# dboard.net
KiCad netlist of a schematic drawn in EAGLE
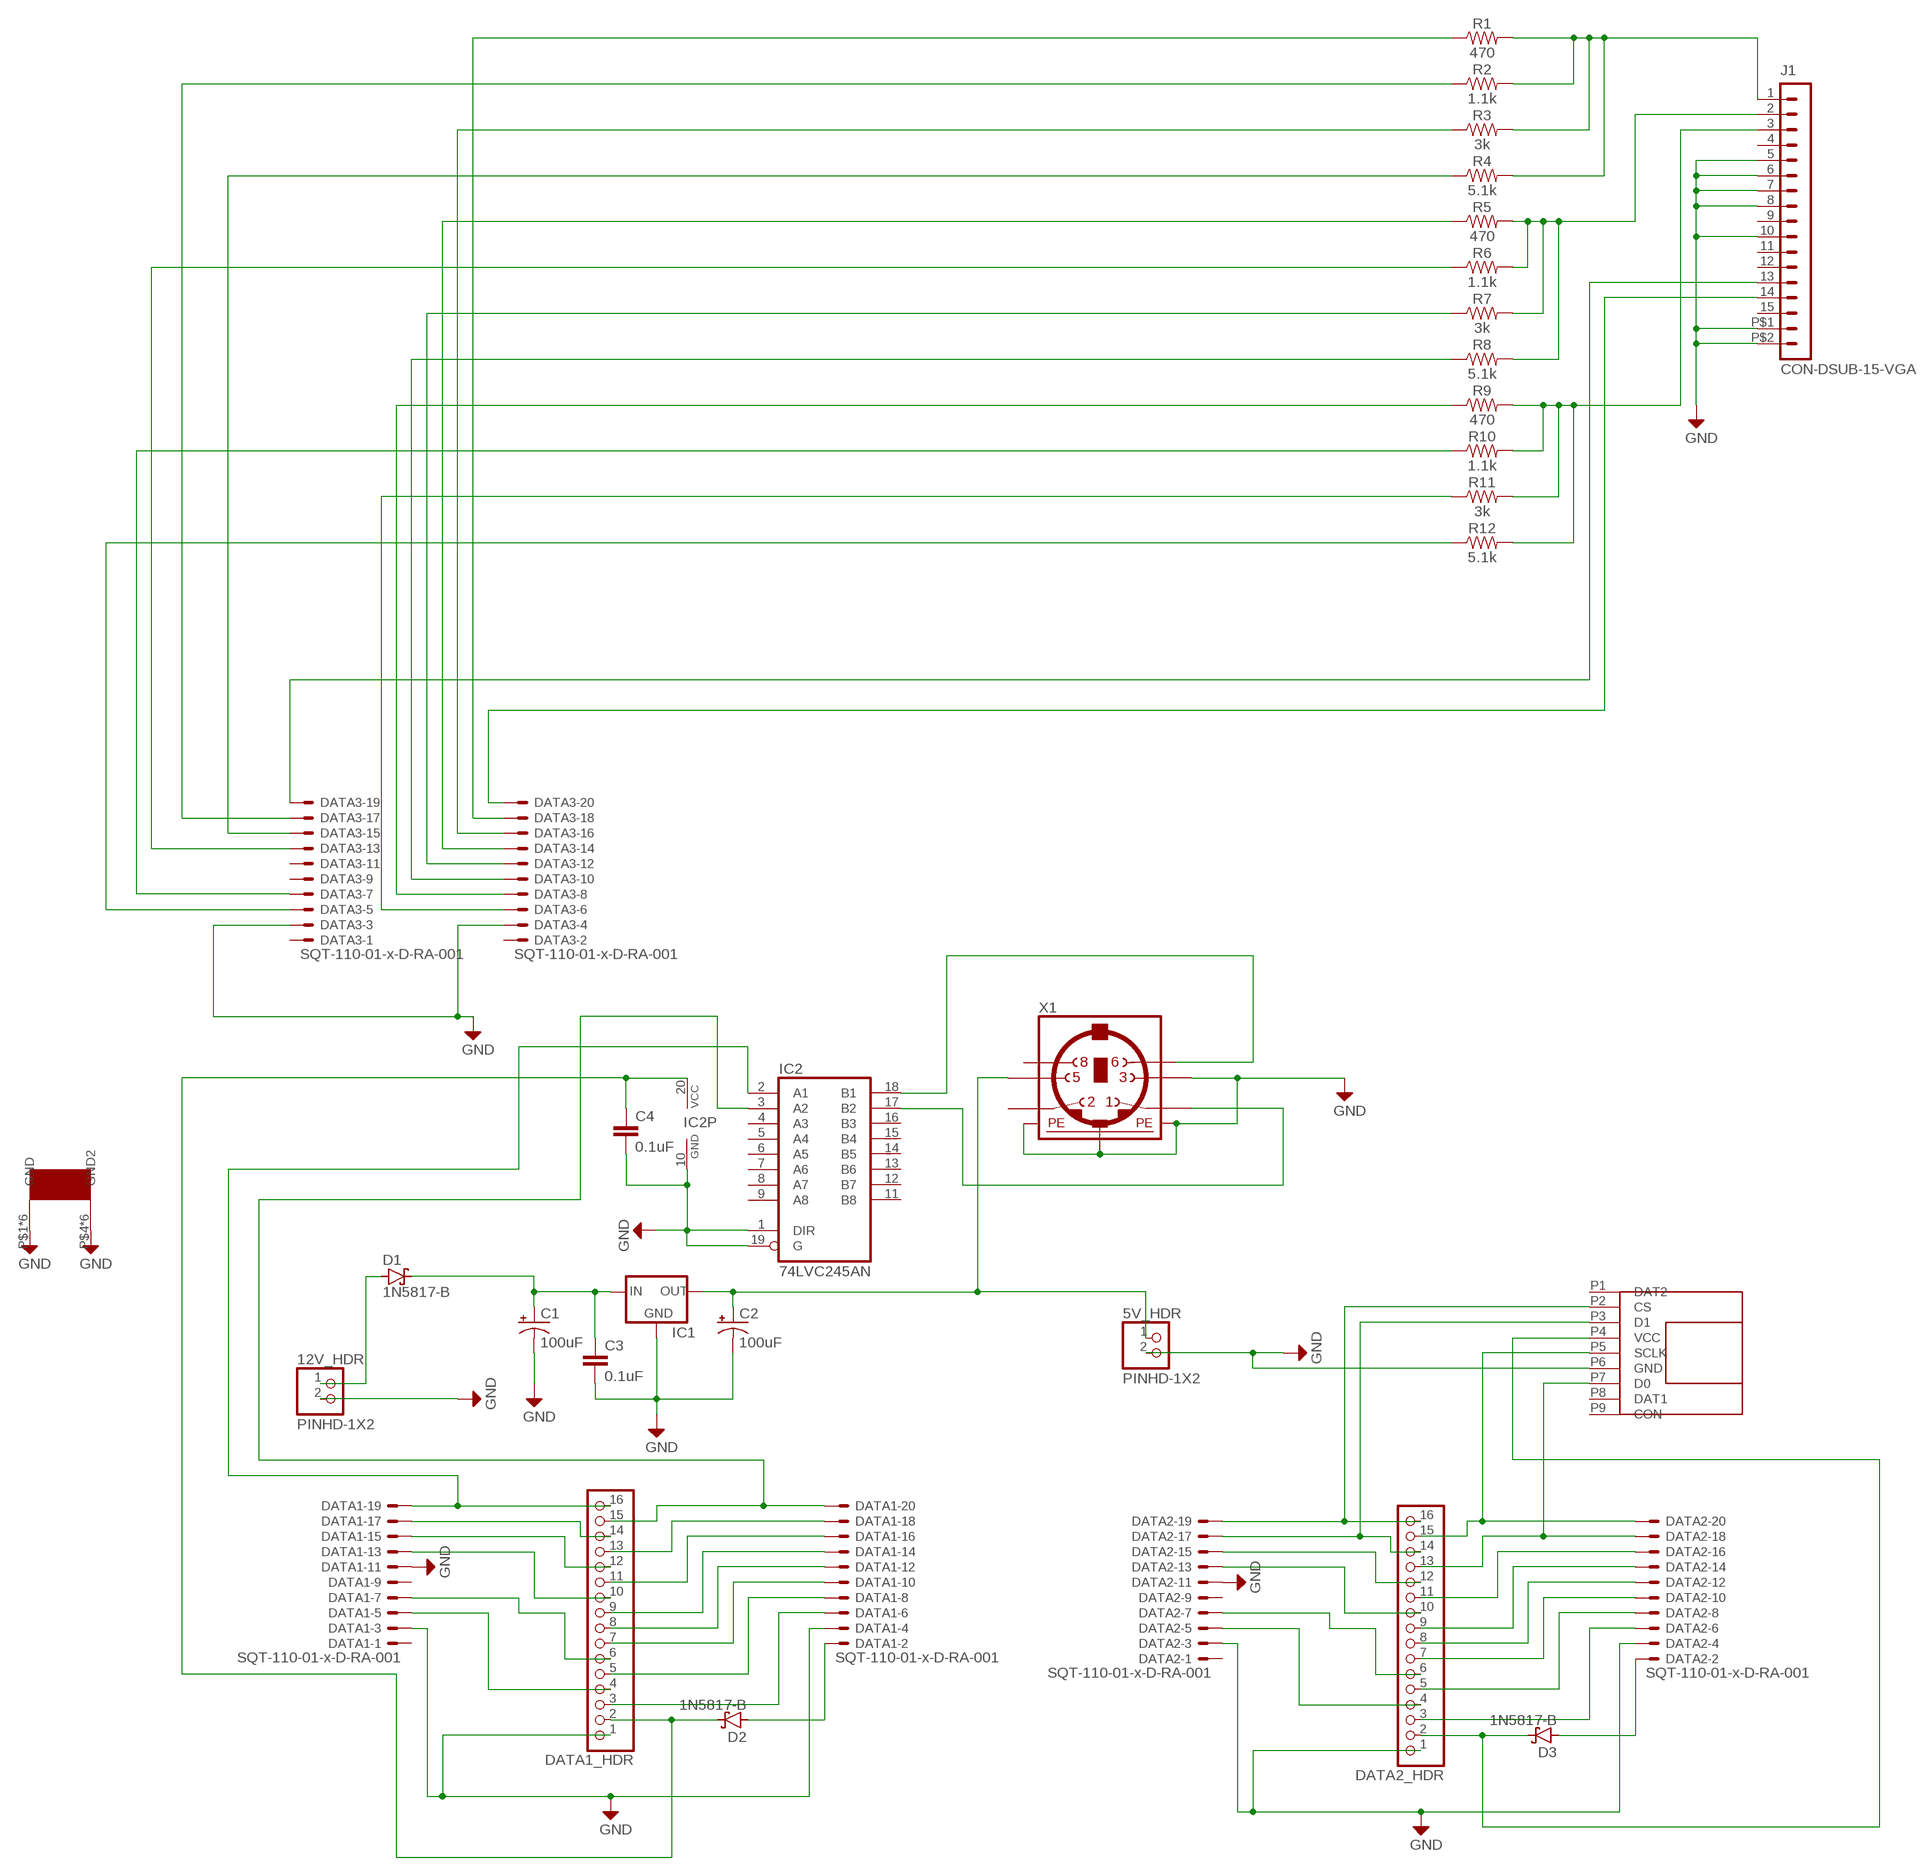
[diagram p0: schematic, sheet 1]

(export (version "E")
  (design (tool "Eeschema 10.0.6"))
  (components
    (comp (ref "5V_HDR")
      (value "PINHD-1X2")
      (footprint "eagle-import:1X02")
      (libsource (lib "eagle-import") (part "PINHD-1X2"))
    )
    (comp (ref "12V_HDR")
      (value "PINHD-1X2")
      (footprint "eagle-import:1X02")
      (libsource (lib "eagle-import") (part "PINHD-1X2"))
    )
    (comp (ref "C1")
      (value "100uF")
      (footprint "eagle-import:CPOL-RADIAL-2.5MM-6.5MM")
      (libsource (lib "eagle-import") (part "100UF-POLAR-RADIAL-2.5MM-25V-20%"))
    )
    (comp (ref "C2")
      (value "100uF")
      (footprint "eagle-import:CPOL-RADIAL-2.5MM-6.5MM")
      (libsource (lib "eagle-import") (part "100UF-POLAR-RADIAL-2.5MM-25V-20%"))
    )
    (comp (ref "C3")
      (value "0.1uF")
      (footprint "eagle-import:CAP-PTH-SMALL-KIT")
      (libsource (lib "eagle-import") (part "0.1UF-KIT-EZ-50V-20%"))
    )
    (comp (ref "C4")
      (value "0.1uF")
      (footprint "eagle-import:CAP-PTH-SMALL-KIT")
      (libsource (lib "eagle-import") (part "0.1UF-KIT-EZ-50V-20%"))
    )
    (comp (ref "D1")
      (value "1N5817-B")
      (footprint "eagle-import:DO41-7.6")
      (libsource (lib "eagle-import") (part "1N5817-B"))
    )
    (comp (ref "D2")
      (value "1N5817-B")
      (footprint "eagle-import:DO41-7.6")
      (libsource (lib "eagle-import") (part "1N5817-B"))
    )
    (comp (ref "D3")
      (value "1N5817-B")
      (footprint "eagle-import:DO41-7.6")
      (libsource (lib "eagle-import") (part "1N5817-B"))
    )
    (comp (ref "DATA1")
      (value "SQT-110-01-x-D-RA-001")
      (footprint "eagle-import:332-20")
      (libsource (lib "eagle-import") (part "332-20"))
    )
    (comp (ref "DATA1_HDR")
      (value "PINHD-1X16")
      (footprint "eagle-import:1X16")
      (libsource (lib "eagle-import") (part "PINHD-1X16"))
    )
    (comp (ref "DATA2")
      (value "SQT-110-01-x-D-RA-001")
      (footprint "eagle-import:332-20")
      (libsource (lib "eagle-import") (part "332-20"))
    )
    (comp (ref "DATA2_HDR")
      (value "PINHD-1X16")
      (footprint "eagle-import:1X16")
      (libsource (lib "eagle-import") (part "PINHD-1X16"))
    )
    (comp (ref "DATA3")
      (value "SQT-110-01-x-D-RA-001")
      (footprint "eagle-import:332-20")
      (libsource (lib "eagle-import") (part "332-20"))
    )
    (comp (ref "IC1")
      (value "78XXL")
      (footprint "eagle-import:78XXL")
      (libsource (lib "eagle-import") (part "78XXL"))
    )
    (comp (ref "IC2")
      (value "74LVC245AN")
      (footprint "eagle-import:DIL20")
      (libsource (lib "eagle-import") (part "74245NLS"))
    )
    (comp (ref "J1")
      (value "CON-DSUB-15-VGA")
      (footprint "eagle-import:181-015-212-171")
      (libsource (lib "eagle-import") (part "CON-DSUB-15-VGA"))
    )
    (comp (ref "R1")
      (value "470")
      (footprint "eagle-import:AXIAL-0.3")
      (libsource (lib "eagle-import") (part "RESISTORAXIAL-0.3"))
    )
    (comp (ref "R2")
      (value "1.1k")
      (footprint "eagle-import:AXIAL-0.3")
      (libsource (lib "eagle-import") (part "RESISTORAXIAL-0.3"))
    )
    (comp (ref "R3")
      (value "3k")
      (footprint "eagle-import:AXIAL-0.3")
      (libsource (lib "eagle-import") (part "RESISTORAXIAL-0.3"))
    )
    (comp (ref "R4")
      (value "5.1k")
      (footprint "eagle-import:AXIAL-0.3")
      (libsource (lib "eagle-import") (part "RESISTORAXIAL-0.3"))
    )
    (comp (ref "R5")
      (value "470")
      (footprint "eagle-import:AXIAL-0.3")
      (libsource (lib "eagle-import") (part "RESISTORAXIAL-0.3"))
    )
    (comp (ref "R6")
      (value "1.1k")
      (footprint "eagle-import:AXIAL-0.3")
      (libsource (lib "eagle-import") (part "RESISTORAXIAL-0.3"))
    )
    (comp (ref "R7")
      (value "3k")
      (footprint "eagle-import:AXIAL-0.3")
      (libsource (lib "eagle-import") (part "RESISTORAXIAL-0.3"))
    )
    (comp (ref "R8")
      (value "5.1k")
      (footprint "eagle-import:AXIAL-0.3")
      (libsource (lib "eagle-import") (part "RESISTORAXIAL-0.3"))
    )
    (comp (ref "R9")
      (value "470")
      (footprint "eagle-import:AXIAL-0.3")
      (libsource (lib "eagle-import") (part "RESISTORAXIAL-0.3"))
    )
    (comp (ref "R10")
      (value "1.1k")
      (footprint "eagle-import:AXIAL-0.3")
      (libsource (lib "eagle-import") (part "RESISTORAXIAL-0.3"))
    )
    (comp (ref "R11")
      (value "3k")
      (footprint "eagle-import:AXIAL-0.3")
      (libsource (lib "eagle-import") (part "RESISTORAXIAL-0.3"))
    )
    (comp (ref "R12")
      (value "5.1k")
      (footprint "eagle-import:AXIAL-0.3")
      (libsource (lib "eagle-import") (part "RESISTORAXIAL-0.3"))
    )
    (comp (ref "U$1")
      (value "7085THERMALPAD")
      (footprint "eagle-import:7805THERMALPAD")
      (libsource (lib "eagle-import") (part "7085THERMALPAD"))
    )
    (comp (ref "U$2")
      (value "TF_CARD_BREAKOUT")
      (footprint "eagle-import:OPEN-SMARTTFCARDBREAKOUT")
      (libsource (lib "eagle-import") (part "OPEN-SMARTTFCARDBREAKOUT"))
    )
    (comp (ref "X1")
      (value "MINI_DIN_6")
      (footprint "eagle-import:M_DIN6")
      (libsource (lib "eagle-import") (part "MINI_DIN_6"))
    )
  )
  (nets
    (net (code "1") (name "GND") (class "Default")
      (node (ref "12V_HDR") (pin "2") (pinfunction "2_2") (pintype "passive"))
      (node (ref "5V_HDR") (pin "2") (pinfunction "2_2") (pintype "passive"))
      (node (ref "C1") (pin "2") (pinfunction "-_2") (pintype "passive"))
      (node (ref "C2") (pin "2") (pinfunction "-_2") (pintype "passive"))
      (node (ref "C3") (pin "2") (pinfunction "2_2") (pintype "passive"))
      (node (ref "C4") (pin "2") (pinfunction "2_2") (pintype "passive"))
      (node (ref "DATA1") (pin "11") (pinfunction "S_11") (pintype "passive"))
      (node (ref "DATA1") (pin "3") (pinfunction "S_3") (pintype "passive"))
      (node (ref "DATA1") (pin "4") (pinfunction "S_4") (pintype "passive"))
      (node (ref "DATA1_HDR") (pin "1") (pinfunction "1_1") (pintype "passive"))
      (node (ref "DATA2") (pin "11") (pinfunction "S_11") (pintype "passive"))
      (node (ref "DATA2") (pin "3") (pinfunction "S_3") (pintype "passive"))
      (node (ref "DATA2") (pin "4") (pinfunction "S_4") (pintype "passive"))
      (node (ref "DATA2_HDR") (pin "1") (pinfunction "1_1") (pintype "passive"))
      (node (ref "DATA3") (pin "3") (pinfunction "S_3") (pintype "passive"))
      (node (ref "DATA3") (pin "4") (pinfunction "S_4") (pintype "passive"))
      (node (ref "IC1") (pin "GND") (pinfunction "GND_GND") (pintype "input"))
      (node (ref "IC2") (pin "1") (pinfunction "DIR_1") (pintype "input"))
      (node (ref "IC2") (pin "10") (pinfunction "GND_10") (pintype "power_in"))
      (node (ref "IC2") (pin "19") (pinfunction "G_19") (pintype "input"))
      (node (ref "J1") (pin "10") (pinfunction "10_10") (pintype "passive"))
      (node (ref "J1") (pin "5") (pinfunction "5_5") (pintype "passive"))
      (node (ref "J1") (pin "6") (pinfunction "6_6") (pintype "passive"))
      (node (ref "J1") (pin "7") (pinfunction "7_7") (pintype "passive"))
      (node (ref "J1") (pin "8") (pinfunction "8_8") (pintype "passive"))
      (node (ref "J1") (pin "P$1") (pinfunction "16_P$1") (pintype "passive"))
      (node (ref "J1") (pin "P$2") (pinfunction "17_P$2") (pintype "passive"))
      (node (ref "U$1") (pin "P$1") (pinfunction "GND_P$1") (pintype "power_in"))
      (node (ref "U$1") (pin "P$10") (pinfunction "GND_P$10") (pintype "power_in"))
      (node (ref "U$1") (pin "P$11") (pinfunction "GND2_P$11") (pintype "power_in"))
      (node (ref "U$1") (pin "P$14") (pinfunction "GND2_P$14") (pintype "power_in"))
      (node (ref "U$1") (pin "P$19") (pinfunction "GND2_P$19") (pintype "power_in"))
      (node (ref "U$1") (pin "P$21") (pinfunction "GND2_P$21") (pintype "power_in"))
      (node (ref "U$1") (pin "P$24") (pinfunction "GND2_P$24") (pintype "power_in"))
      (node (ref "U$1") (pin "P$4") (pinfunction "GND2_P$4") (pintype "power_in"))
      (node (ref "U$1") (pin "P$6") (pinfunction "GND_P$6") (pintype "power_in"))
      (node (ref "U$1") (pin "P$7") (pinfunction "GND_P$7") (pintype "power_in"))
      (node (ref "U$1") (pin "P$8") (pinfunction "GND_P$8") (pintype "power_in"))
      (node (ref "U$1") (pin "P$9") (pinfunction "GND_P$9") (pintype "power_in"))
      (node (ref "U$2") (pin "P6") (pinfunction "GND_P6") (pintype "power_in"))
      (node (ref "X1") (pin "3") (pinfunction "3_3") (pintype "passive"))
      (node (ref "X1") (pin "SH1") (pinfunction "PE1_SH1") (pintype "power_in"))
      (node (ref "X1") (pin "SH2") (pinfunction "PE2_SH2") (pintype "power_in"))
      (node (ref "X1") (pin "SH3") (pinfunction "PE3_SH3") (pintype "power_in"))
    )
    (net (code "2") (name "Net-(12V_HDR-Pad1)") (class "Default")
      (node (ref "12V_HDR") (pin "1") (pinfunction "1_1") (pintype "passive"))
      (node (ref "D1") (pin "A") (pinfunction "A_A") (pintype "passive"))
    )
    (net (code "3") (name "Net-(C1-+)") (class "Default")
      (node (ref "C1") (pin "1") (pinfunction "+_1") (pintype "passive"))
      (node (ref "C3") (pin "1") (pinfunction "1_1") (pintype "passive"))
      (node (ref "D1") (pin "C") (pinfunction "C_C") (pintype "passive"))
      (node (ref "IC1") (pin "IN") (pinfunction "IN_IN") (pintype "input"))
    )
    (net (code "4") (name "Net-(C2-+)") (class "Default")
      (node (ref "5V_HDR") (pin "1") (pinfunction "1_1") (pintype "passive"))
      (node (ref "C2") (pin "1") (pinfunction "+_1") (pintype "passive"))
      (node (ref "IC1") (pin "OUT") (pinfunction "OUT_OUT") (pintype "passive"))
      (node (ref "X1") (pin "5") (pinfunction "5_5") (pintype "passive"))
    )
    (net (code "5") (name "Net-(DATA1B-S)") (class "Default")
      (node (ref "DATA1") (pin "10") (pinfunction "S_10") (pintype "passive"))
      (node (ref "DATA1_HDR") (pin "7") (pinfunction "7_7") (pintype "passive"))
    )
    (net (code "6") (name "Net-(DATA1D-S)") (class "Default")
      (node (ref "DATA1") (pin "12") (pinfunction "S_12") (pintype "passive"))
      (node (ref "DATA1_HDR") (pin "8") (pinfunction "8_8") (pintype "passive"))
    )
    (net (code "7") (name "Net-(DATA1E-S)") (class "Default")
      (node (ref "DATA1") (pin "13") (pinfunction "S_13") (pintype "passive"))
      (node (ref "DATA1_HDR") (pin "10") (pinfunction "10_10") (pintype "passive"))
    )
    (net (code "8") (name "Net-(DATA1F-S)") (class "Default")
      (node (ref "DATA1") (pin "14") (pinfunction "S_14") (pintype "passive"))
      (node (ref "DATA1_HDR") (pin "9") (pinfunction "9_9") (pintype "passive"))
    )
    (net (code "9") (name "Net-(DATA1G-S)") (class "Default")
      (node (ref "DATA1") (pin "15") (pinfunction "S_15") (pintype "passive"))
      (node (ref "DATA1_HDR") (pin "12") (pinfunction "12_12") (pintype "passive"))
    )
    (net (code "10") (name "Net-(DATA1H-S)") (class "Default")
      (node (ref "DATA1") (pin "16") (pinfunction "S_16") (pintype "passive"))
      (node (ref "DATA1_HDR") (pin "11") (pinfunction "11_11") (pintype "passive"))
    )
    (net (code "11") (name "Net-(DATA1I-S)") (class "Default")
      (node (ref "DATA1") (pin "17") (pinfunction "S_17") (pintype "passive"))
      (node (ref "DATA1_HDR") (pin "14") (pinfunction "14_14") (pintype "passive"))
    )
    (net (code "12") (name "Net-(DATA1J-S)") (class "Default")
      (node (ref "DATA1") (pin "18") (pinfunction "S_18") (pintype "passive"))
      (node (ref "DATA1_HDR") (pin "13") (pinfunction "13_13") (pintype "passive"))
    )
    (net (code "13") (name "Net-(DATA1K-S)") (class "Default")
      (node (ref "DATA1") (pin "19") (pinfunction "S_19") (pintype "passive"))
      (node (ref "DATA1_HDR") (pin "16") (pinfunction "16_16") (pintype "passive"))
      (node (ref "IC2") (pin "2") (pinfunction "A1_2") (pintype "bidirectional"))
    )
    (net (code "14") (name "Net-(DATA1L-S)") (class "Default")
      (node (ref "D2") (pin "A") (pinfunction "A_A") (pintype "passive"))
      (node (ref "DATA1") (pin "2") (pinfunction "S_2") (pintype "passive"))
    )
    (net (code "15") (name "Net-(DATA1M-S)") (class "Default")
      (node (ref "DATA1") (pin "20") (pinfunction "S_20") (pintype "passive"))
      (node (ref "DATA1_HDR") (pin "15") (pinfunction "15_15") (pintype "passive"))
      (node (ref "IC2") (pin "3") (pinfunction "A2_3") (pintype "bidirectional"))
    )
    (net (code "16") (name "Net-(DATA1P-S)") (class "Default")
      (node (ref "DATA1") (pin "5") (pinfunction "S_5") (pintype "passive"))
      (node (ref "DATA1_HDR") (pin "4") (pinfunction "4_4") (pintype "passive"))
    )
    (net (code "17") (name "Net-(DATA1Q-S)") (class "Default")
      (node (ref "DATA1") (pin "6") (pinfunction "S_6") (pintype "passive"))
      (node (ref "DATA1_HDR") (pin "3") (pinfunction "3_3") (pintype "passive"))
    )
    (net (code "18") (name "Net-(DATA1R-S)") (class "Default")
      (node (ref "DATA1") (pin "7") (pinfunction "S_7") (pintype "passive"))
      (node (ref "DATA1_HDR") (pin "6") (pinfunction "6_6") (pintype "passive"))
    )
    (net (code "19") (name "Net-(DATA1S-S)") (class "Default")
      (node (ref "DATA1") (pin "8") (pinfunction "S_8") (pintype "passive"))
      (node (ref "DATA1_HDR") (pin "5") (pinfunction "5_5") (pintype "passive"))
    )
    (net (code "20") (name "Net-(DATA2B-S)") (class "Default")
      (node (ref "DATA2") (pin "10") (pinfunction "S_10") (pintype "passive"))
      (node (ref "DATA2_HDR") (pin "7") (pinfunction "7_7") (pintype "passive"))
    )
    (net (code "21") (name "Net-(DATA2D-S)") (class "Default")
      (node (ref "DATA2") (pin "12") (pinfunction "S_12") (pintype "passive"))
      (node (ref "DATA2_HDR") (pin "8") (pinfunction "8_8") (pintype "passive"))
    )
    (net (code "22") (name "Net-(DATA2E-S)") (class "Default")
      (node (ref "DATA2") (pin "13") (pinfunction "S_13") (pintype "passive"))
      (node (ref "DATA2_HDR") (pin "10") (pinfunction "10_10") (pintype "passive"))
    )
    (net (code "23") (name "Net-(DATA2F-S)") (class "Default")
      (node (ref "DATA2") (pin "14") (pinfunction "S_14") (pintype "passive"))
      (node (ref "DATA2_HDR") (pin "9") (pinfunction "9_9") (pintype "passive"))
    )
    (net (code "24") (name "Net-(DATA2G-S)") (class "Default")
      (node (ref "DATA2") (pin "15") (pinfunction "S_15") (pintype "passive"))
      (node (ref "DATA2_HDR") (pin "12") (pinfunction "12_12") (pintype "passive"))
    )
    (net (code "25") (name "Net-(DATA2H-S)") (class "Default")
      (node (ref "DATA2") (pin "16") (pinfunction "S_16") (pintype "passive"))
      (node (ref "DATA2_HDR") (pin "11") (pinfunction "11_11") (pintype "passive"))
    )
    (net (code "26") (name "Net-(DATA2I-S)") (class "Default")
      (node (ref "DATA2") (pin "17") (pinfunction "S_17") (pintype "passive"))
      (node (ref "DATA2_HDR") (pin "14") (pinfunction "14_14") (pintype "passive"))
      (node (ref "U$2") (pin "P3") (pinfunction "D1_P3") (pintype "input"))
    )
    (net (code "27") (name "Net-(DATA2J-S)") (class "Default")
      (node (ref "DATA2") (pin "18") (pinfunction "S_18") (pintype "passive"))
      (node (ref "DATA2_HDR") (pin "13") (pinfunction "13_13") (pintype "passive"))
      (node (ref "U$2") (pin "P7") (pinfunction "D0_P7") (pintype "bidirectional"))
    )
    (net (code "28") (name "Net-(DATA2K-S)") (class "Default")
      (node (ref "DATA2") (pin "19") (pinfunction "S_19") (pintype "passive"))
      (node (ref "DATA2_HDR") (pin "16") (pinfunction "16_16") (pintype "passive"))
      (node (ref "U$2") (pin "P2") (pinfunction "CS_P2") (pintype "input"))
    )
    (net (code "29") (name "Net-(DATA2L-S)") (class "Default")
      (node (ref "D3") (pin "A") (pinfunction "A_A") (pintype "passive"))
      (node (ref "DATA2") (pin "2") (pinfunction "S_2") (pintype "passive"))
    )
    (net (code "30") (name "Net-(DATA2M-S)") (class "Default")
      (node (ref "DATA2") (pin "20") (pinfunction "S_20") (pintype "passive"))
      (node (ref "DATA2_HDR") (pin "15") (pinfunction "15_15") (pintype "passive"))
      (node (ref "U$2") (pin "P5") (pinfunction "SCLK_P5") (pintype "input"))
    )
    (net (code "31") (name "Net-(DATA2P-S)") (class "Default")
      (node (ref "DATA2") (pin "5") (pinfunction "S_5") (pintype "passive"))
      (node (ref "DATA2_HDR") (pin "4") (pinfunction "4_4") (pintype "passive"))
    )
    (net (code "32") (name "Net-(DATA2Q-S)") (class "Default")
      (node (ref "DATA2") (pin "6") (pinfunction "S_6") (pintype "passive"))
      (node (ref "DATA2_HDR") (pin "3") (pinfunction "3_3") (pintype "passive"))
    )
    (net (code "33") (name "Net-(DATA2R-S)") (class "Default")
      (node (ref "DATA2") (pin "7") (pinfunction "S_7") (pintype "passive"))
      (node (ref "DATA2_HDR") (pin "6") (pinfunction "6_6") (pintype "passive"))
    )
    (net (code "34") (name "Net-(DATA2S-S)") (class "Default")
      (node (ref "DATA2") (pin "8") (pinfunction "S_8") (pintype "passive"))
      (node (ref "DATA2_HDR") (pin "5") (pinfunction "5_5") (pintype "passive"))
    )
    (net (code "35") (name "Net-(DATA3B-S)") (class "Default")
      (node (ref "DATA3") (pin "10") (pinfunction "S_10") (pintype "passive"))
      (node (ref "R8") (pin "P$1") (pinfunction "1_P$1") (pintype "passive"))
    )
    (net (code "36") (name "Net-(DATA3D-S)") (class "Default")
      (node (ref "DATA3") (pin "12") (pinfunction "S_12") (pintype "passive"))
      (node (ref "R7") (pin "P$1") (pinfunction "1_P$1") (pintype "passive"))
    )
    (net (code "37") (name "Net-(DATA3E-S)") (class "Default")
      (node (ref "DATA3") (pin "13") (pinfunction "S_13") (pintype "passive"))
      (node (ref "R6") (pin "P$1") (pinfunction "1_P$1") (pintype "passive"))
    )
    (net (code "38") (name "Net-(DATA3F-S)") (class "Default")
      (node (ref "DATA3") (pin "14") (pinfunction "S_14") (pintype "passive"))
      (node (ref "R5") (pin "P$1") (pinfunction "1_P$1") (pintype "passive"))
    )
    (net (code "39") (name "Net-(DATA3G-S)") (class "Default")
      (node (ref "DATA3") (pin "15") (pinfunction "S_15") (pintype "passive"))
      (node (ref "R4") (pin "P$1") (pinfunction "1_P$1") (pintype "passive"))
    )
    (net (code "40") (name "Net-(DATA3H-S)") (class "Default")
      (node (ref "DATA3") (pin "16") (pinfunction "S_16") (pintype "passive"))
      (node (ref "R3") (pin "P$1") (pinfunction "1_P$1") (pintype "passive"))
    )
    (net (code "41") (name "Net-(DATA3I-S)") (class "Default")
      (node (ref "DATA3") (pin "17") (pinfunction "S_17") (pintype "passive"))
      (node (ref "R2") (pin "P$1") (pinfunction "1_P$1") (pintype "passive"))
    )
    (net (code "42") (name "Net-(DATA3J-S)") (class "Default")
      (node (ref "DATA3") (pin "18") (pinfunction "S_18") (pintype "passive"))
      (node (ref "R1") (pin "P$1") (pinfunction "1_P$1") (pintype "passive"))
    )
    (net (code "43") (name "Net-(DATA3K-S)") (class "Default")
      (node (ref "DATA3") (pin "19") (pinfunction "S_19") (pintype "passive"))
      (node (ref "J1") (pin "13") (pinfunction "13_13") (pintype "passive"))
    )
    (net (code "44") (name "Net-(DATA3M-S)") (class "Default")
      (node (ref "DATA3") (pin "20") (pinfunction "S_20") (pintype "passive"))
      (node (ref "J1") (pin "14") (pinfunction "14_14") (pintype "passive"))
    )
    (net (code "45") (name "Net-(DATA3P-S)") (class "Default")
      (node (ref "DATA3") (pin "5") (pinfunction "S_5") (pintype "passive"))
      (node (ref "R12") (pin "P$1") (pinfunction "1_P$1") (pintype "passive"))
    )
    (net (code "46") (name "Net-(DATA3Q-S)") (class "Default")
      (node (ref "DATA3") (pin "6") (pinfunction "S_6") (pintype "passive"))
      (node (ref "R11") (pin "P$1") (pinfunction "1_P$1") (pintype "passive"))
    )
    (net (code "47") (name "Net-(DATA3R-S)") (class "Default")
      (node (ref "DATA3") (pin "7") (pinfunction "S_7") (pintype "passive"))
      (node (ref "R10") (pin "P$1") (pinfunction "1_P$1") (pintype "passive"))
    )
    (net (code "48") (name "Net-(DATA3S-S)") (class "Default")
      (node (ref "DATA3") (pin "8") (pinfunction "S_8") (pintype "passive"))
      (node (ref "R9") (pin "P$1") (pinfunction "1_P$1") (pintype "passive"))
    )
    (net (code "49") (name "Net-(IC2A-B1)") (class "Default")
      (node (ref "IC2") (pin "18") (pinfunction "B1_18") (pintype "bidirectional"))
      (node (ref "X1") (pin "6") (pinfunction "6_6") (pintype "passive"))
    )
    (net (code "50") (name "Net-(IC2A-B2)") (class "Default")
      (node (ref "IC2") (pin "17") (pinfunction "B2_17") (pintype "bidirectional"))
      (node (ref "X1") (pin "1") (pinfunction "1_1") (pintype "passive"))
    )
    (net (code "51") (name "Net-(IC2B-VCC)") (class "Default")
      (node (ref "C4") (pin "1") (pinfunction "1_1") (pintype "passive"))
      (node (ref "D2") (pin "C") (pinfunction "C_C") (pintype "passive"))
      (node (ref "DATA1_HDR") (pin "2") (pinfunction "2_2") (pintype "passive"))
      (node (ref "IC2") (pin "20") (pinfunction "VCC_20") (pintype "power_in"))
    )
    (net (code "52") (name "Net-(R1-2)") (class "Default")
      (node (ref "J1") (pin "1") (pinfunction "1_1") (pintype "passive"))
      (node (ref "R1") (pin "P$2") (pinfunction "2_P$2") (pintype "passive"))
      (node (ref "R2") (pin "P$2") (pinfunction "2_P$2") (pintype "passive"))
      (node (ref "R3") (pin "P$2") (pinfunction "2_P$2") (pintype "passive"))
      (node (ref "R4") (pin "P$2") (pinfunction "2_P$2") (pintype "passive"))
    )
    (net (code "53") (name "Net-(R5-2)") (class "Default")
      (node (ref "J1") (pin "2") (pinfunction "2_2") (pintype "passive"))
      (node (ref "R5") (pin "P$2") (pinfunction "2_P$2") (pintype "passive"))
      (node (ref "R6") (pin "P$2") (pinfunction "2_P$2") (pintype "passive"))
      (node (ref "R7") (pin "P$2") (pinfunction "2_P$2") (pintype "passive"))
      (node (ref "R8") (pin "P$2") (pinfunction "2_P$2") (pintype "passive"))
    )
    (net (code "54") (name "Net-(R10-2)") (class "Default")
      (node (ref "J1") (pin "3") (pinfunction "3_3") (pintype "passive"))
      (node (ref "R10") (pin "P$2") (pinfunction "2_P$2") (pintype "passive"))
      (node (ref "R11") (pin "P$2") (pinfunction "2_P$2") (pintype "passive"))
      (node (ref "R12") (pin "P$2") (pinfunction "2_P$2") (pintype "passive"))
      (node (ref "R9") (pin "P$2") (pinfunction "2_P$2") (pintype "passive"))
    )
    (net (code "55") (name "Net-(U$2-VCC)") (class "Default")
      (node (ref "D3") (pin "C") (pinfunction "C_C") (pintype "passive"))
      (node (ref "DATA2_HDR") (pin "2") (pinfunction "2_2") (pintype "passive"))
      (node (ref "U$2") (pin "P4") (pinfunction "VCC_P4") (pintype "power_in"))
    )
    (net (code "56") (name "unconnected-(DATA1A-S-Pad1)") (class "Default")
      (node (ref "DATA1") (pin "1") (pinfunction "S_1") (pintype "passive"))
    )
    (net (code "57") (name "unconnected-(DATA1T-S-Pad9)") (class "Default")
      (node (ref "DATA1") (pin "9") (pinfunction "S_9") (pintype "passive"))
    )
    (net (code "58") (name "unconnected-(DATA2A-S-Pad1)") (class "Default")
      (node (ref "DATA2") (pin "1") (pinfunction "S_1") (pintype "passive"))
    )
    (net (code "59") (name "unconnected-(DATA2T-S-Pad9)") (class "Default")
      (node (ref "DATA2") (pin "9") (pinfunction "S_9") (pintype "passive"))
    )
    (net (code "60") (name "unconnected-(DATA3A-S-Pad1)") (class "Default")
      (node (ref "DATA3") (pin "1") (pinfunction "S_1") (pintype "passive"))
    )
    (net (code "61") (name "unconnected-(DATA3C-S-Pad11)") (class "Default")
      (node (ref "DATA3") (pin "11") (pinfunction "S_11") (pintype "passive"))
    )
    (net (code "62") (name "unconnected-(DATA3L-S-Pad2)") (class "Default")
      (node (ref "DATA3") (pin "2") (pinfunction "S_2") (pintype "passive"))
    )
    (net (code "63") (name "unconnected-(DATA3T-S-Pad9)") (class "Default")
      (node (ref "DATA3") (pin "9") (pinfunction "S_9") (pintype "passive"))
    )
    (net (code "64") (name "unconnected-(IC2A-A3-Pad4)") (class "Default")
      (node (ref "IC2") (pin "4") (pinfunction "A3_4") (pintype "bidirectional"))
    )
    (net (code "65") (name "unconnected-(IC2A-A4-Pad5)") (class "Default")
      (node (ref "IC2") (pin "5") (pinfunction "A4_5") (pintype "bidirectional"))
    )
    (net (code "66") (name "unconnected-(IC2A-A5-Pad6)") (class "Default")
      (node (ref "IC2") (pin "6") (pinfunction "A5_6") (pintype "bidirectional"))
    )
    (net (code "67") (name "unconnected-(IC2A-A6-Pad7)") (class "Default")
      (node (ref "IC2") (pin "7") (pinfunction "A6_7") (pintype "bidirectional"))
    )
    (net (code "68") (name "unconnected-(IC2A-A7-Pad8)") (class "Default")
      (node (ref "IC2") (pin "8") (pinfunction "A7_8") (pintype "bidirectional"))
    )
    (net (code "69") (name "unconnected-(IC2A-A8-Pad9)") (class "Default")
      (node (ref "IC2") (pin "9") (pinfunction "A8_9") (pintype "bidirectional"))
    )
    (net (code "70") (name "unconnected-(IC2A-B3-Pad16)") (class "Default")
      (node (ref "IC2") (pin "16") (pinfunction "B3_16") (pintype "bidirectional"))
    )
    (net (code "71") (name "unconnected-(IC2A-B4-Pad15)") (class "Default")
      (node (ref "IC2") (pin "15") (pinfunction "B4_15") (pintype "bidirectional"))
    )
    (net (code "72") (name "unconnected-(IC2A-B5-Pad14)") (class "Default")
      (node (ref "IC2") (pin "14") (pinfunction "B5_14") (pintype "bidirectional"))
    )
    (net (code "73") (name "unconnected-(IC2A-B6-Pad13)") (class "Default")
      (node (ref "IC2") (pin "13") (pinfunction "B6_13") (pintype "bidirectional"))
    )
    (net (code "74") (name "unconnected-(IC2A-B7-Pad12)") (class "Default")
      (node (ref "IC2") (pin "12") (pinfunction "B7_12") (pintype "bidirectional"))
    )
    (net (code "75") (name "unconnected-(IC2A-B8-Pad11)") (class "Default")
      (node (ref "IC2") (pin "11") (pinfunction "B8_11") (pintype "bidirectional"))
    )
    (net (code "76") (name "unconnected-(J1-Pad4)") (class "Default")
      (node (ref "J1") (pin "4") (pinfunction "4_4") (pintype "passive"))
    )
    (net (code "77") (name "unconnected-(J1-Pad9)") (class "Default")
      (node (ref "J1") (pin "9") (pinfunction "9_9") (pintype "passive"))
    )
    (net (code "78") (name "unconnected-(J1-Pad11)") (class "Default")
      (node (ref "J1") (pin "11") (pinfunction "11_11") (pintype "passive"))
    )
    (net (code "79") (name "unconnected-(J1-Pad12)") (class "Default")
      (node (ref "J1") (pin "12") (pinfunction "12_12") (pintype "passive"))
    )
    (net (code "80") (name "unconnected-(J1-Pad15)") (class "Default")
      (node (ref "J1") (pin "15") (pinfunction "15_15") (pintype "passive"))
    )
    (net (code "81") (name "unconnected-(U$2-CON-PadP9)") (class "Default")
      (node (ref "U$2") (pin "P9") (pinfunction "CON_P9") (pintype "bidirectional"))
    )
    (net (code "82") (name "unconnected-(U$2-DAT1-PadP8)") (class "Default")
      (node (ref "U$2") (pin "P8") (pinfunction "DAT1_P8") (pintype "bidirectional"))
    )
    (net (code "83") (name "unconnected-(U$2-DAT2-PadP1)") (class "Default")
      (node (ref "U$2") (pin "P1") (pinfunction "DAT2_P1") (pintype "bidirectional"))
    )
    (net (code "84") (name "unconnected-(X1-Pad2)") (class "Default")
      (node (ref "X1") (pin "2") (pinfunction "2_2") (pintype "passive"))
    )
    (net (code "85") (name "unconnected-(X1-Pad8)") (class "Default")
      (node (ref "X1") (pin "8") (pinfunction "8_8") (pintype "passive"))
    )
  )
)
